# 02_ZYNQ_PS-BANK500-501.net
KiCad netlist of a schematic drawn in Altium Designer
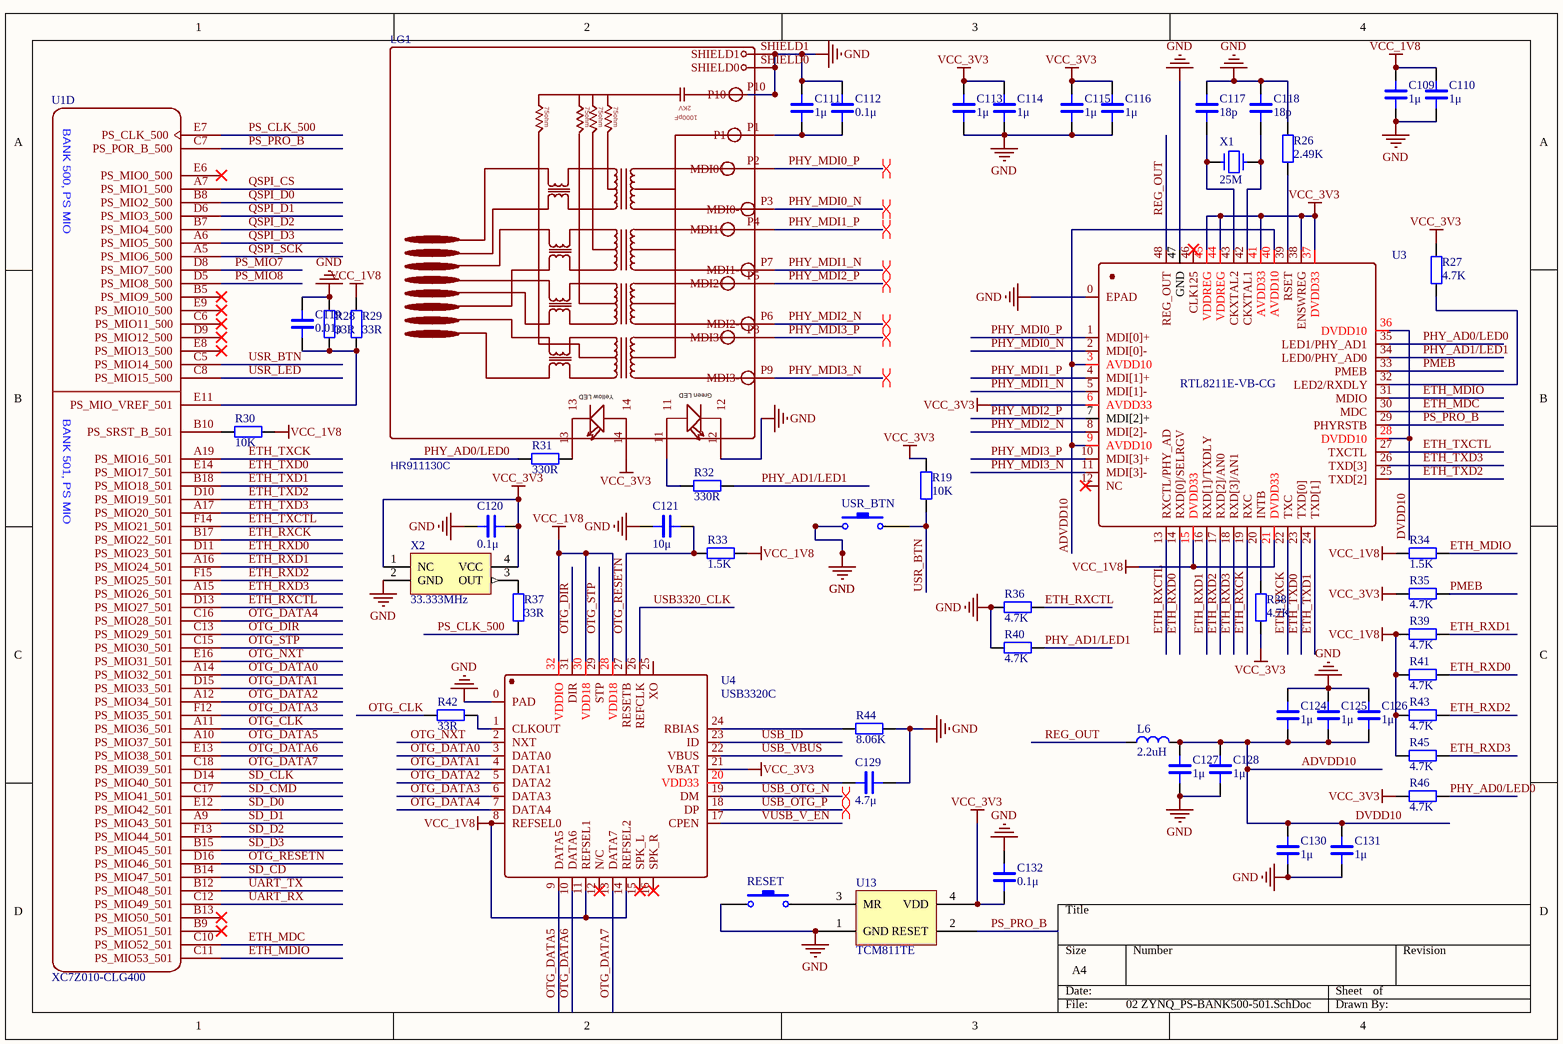
[diagram p0: 02 ZYNQ_PS-BANK500-501.SchDoc]

(export (version "E")
  (design (tool "Eeschema 10.0.6"))
  (components
    (comp (ref "C109")
      (value "1μ")
      (footprint "LC-0402_C")
      (description "Capacitor")
      (libsource (lib "DDR3_xc7z010-clg400") (part "CAP_2"))
    )
    (comp (ref "C110")
      (value "1μ")
      (footprint "LC-0402_C")
      (description "Capacitor")
      (libsource (lib "DDR3_xc7z010-clg400") (part "CAP_2"))
    )
    (comp (ref "C111")
      (value "1μ")
      (footprint "LC-0402_C")
      (description "Capacitor")
      (libsource (lib "DDR3_xc7z010-clg400") (part "CAP_2"))
    )
    (comp (ref "C112")
      (value "0.1μ")
      (footprint "LC-0402_C")
      (description "Capacitor")
      (libsource (lib "DDR3_xc7z010-clg400") (part "CAP_2"))
    )
    (comp (ref "C113")
      (value "1μ")
      (footprint "LC-0402_C")
      (description "Capacitor")
      (libsource (lib "DDR3_xc7z010-clg400") (part "CAP_2"))
    )
    (comp (ref "C114")
      (value "1μ")
      (footprint "LC-0402_C")
      (description "Capacitor")
      (libsource (lib "DDR3_xc7z010-clg400") (part "CAP_2"))
    )
    (comp (ref "C115")
      (value "1μ")
      (footprint "LC-0402_C")
      (description "Capacitor")
      (libsource (lib "DDR3_xc7z010-clg400") (part "CAP_2"))
    )
    (comp (ref "C116")
      (value "1μ")
      (footprint "LC-0402_C")
      (description "Capacitor")
      (libsource (lib "DDR3_xc7z010-clg400") (part "CAP_2"))
    )
    (comp (ref "C117")
      (value "18p")
      (footprint "LC-0402_C")
      (description "Capacitor")
      (libsource (lib "DDR3_xc7z010-clg400") (part "CAP_1"))
    )
    (comp (ref "C118")
      (value "18p")
      (footprint "LC-0402_C")
      (description "Capacitor")
      (libsource (lib "DDR3_xc7z010-clg400") (part "CAP_1"))
    )
    (comp (ref "C119")
      (value "0.01μ")
      (footprint "LC-0402_C")
      (description "Capacitor")
      (libsource (lib "DDR3_xc7z010-clg400") (part "CAP_2"))
    )
    (comp (ref "C120")
      (value "0.1μ")
      (footprint "LC-0402_C")
      (description "Capacitor")
      (libsource (lib "DDR3_xc7z010-clg400") (part "CAP_2"))
    )
    (comp (ref "C121")
      (value "10μ")
      (footprint "LC-0402_C")
      (description "Capacitor")
      (libsource (lib "DDR3_xc7z010-clg400") (part "CAP_2"))
    )
    (comp (ref "C124")
      (value "1μ")
      (footprint "LC-0402_C")
      (description "Capacitor")
      (libsource (lib "DDR3_xc7z010-clg400") (part "CAP_2"))
    )
    (comp (ref "C125")
      (value "1μ")
      (footprint "LC-0402_C")
      (description "Capacitor")
      (libsource (lib "DDR3_xc7z010-clg400") (part "CAP_2"))
    )
    (comp (ref "C126")
      (value "1μ")
      (footprint "LC-0402_C")
      (description "Capacitor")
      (libsource (lib "DDR3_xc7z010-clg400") (part "CAP_2"))
    )
    (comp (ref "C127")
      (value "1μ")
      (footprint "LC-0402_C")
      (description "Capacitor")
      (libsource (lib "DDR3_xc7z010-clg400") (part "CAP_2"))
    )
    (comp (ref "C128")
      (value "1μ")
      (footprint "LC-0402_C")
      (description "Capacitor")
      (libsource (lib "DDR3_xc7z010-clg400") (part "CAP_2"))
    )
    (comp (ref "C129")
      (value "4.7μ")
      (footprint "LC-0402_C")
      (description "Capacitor")
      (libsource (lib "DDR3_xc7z010-clg400") (part "CAP_2"))
    )
    (comp (ref "C130")
      (value "1μ")
      (footprint "LC-0402_C")
      (description "Capacitor")
      (libsource (lib "DDR3_xc7z010-clg400") (part "CAP_2"))
    )
    (comp (ref "C131")
      (value "1μ")
      (footprint "LC-0402_C")
      (description "Capacitor")
      (libsource (lib "DDR3_xc7z010-clg400") (part "CAP_2"))
    )
    (comp (ref "C132")
      (value "0.1μ")
      (footprint "LC-0402_C")
      (description "Capacitor")
      (libsource (lib "DDR3_xc7z010-clg400") (part "CAP_2"))
    )
    (comp (ref "L6")
      (value "2.2uH")
      (footprint "L1008")
      (description "Inductance")
      (libsource (lib "NGFF_M_Key_xc7z010-clg400") (part "INDUCTANCE_1"))
    )
    (comp (ref "LG1")
      (value "HR911130C")
      (footprint "HR911130C")
      (fields (field (name "BOM_SUPPLIER PART") "C50933") (field (name "CONTRIBUTOR") "LCSC"))
      (libsource (lib "AD9363_ZYNQ_V2") (part "HR911130C"))
    )
    (comp (ref "R19")
      (value "10K")
      (footprint "LC-0402_R")
      (description "Resistor")
      (libsource (lib "") (part "RES_3"))
    )
    (comp (ref "R26")
      (value "2.49K")
      (footprint "LC-0402_R")
      (description "Resistor")
      (libsource (lib "") (part "RES_2"))
    )
    (comp (ref "R27")
      (value "4.7K")
      (footprint "LC-0402_R")
      (description "Resistor")
      (libsource (lib "") (part "RES_2"))
    )
    (comp (ref "R28")
      (value "33R")
      (footprint "LC-0402_R")
      (description "Resistor")
      (libsource (lib "") (part "RES_2"))
    )
    (comp (ref "R29")
      (value "33R")
      (footprint "LC-0402_R")
      (description "Resistor")
      (libsource (lib "") (part "RES_2"))
    )
    (comp (ref "R30")
      (value "10K")
      (footprint "LC-0402_R")
      (description "Resistor")
      (libsource (lib "") (part "RES_1"))
    )
    (comp (ref "R31")
      (value "330R")
      (footprint "LC-0402_R")
      (description "Resistor")
      (libsource (lib "DDR3_xc7z010-clg400") (part "RES"))
    )
    (comp (ref "R32")
      (value "330R")
      (footprint "LC-0402_R")
      (description "Resistor")
      (libsource (lib "") (part "RES_1"))
    )
    (comp (ref "R33")
      (value "1.5K")
      (footprint "LC-0402_R")
      (description "Resistor")
      (libsource (lib "DDR3_xc7z010-clg400") (part "RES"))
    )
    (comp (ref "R34")
      (value "1.5K")
      (footprint "LC-0402_R")
      (description "Resistor")
      (libsource (lib "DDR3_xc7z010-clg400") (part "RES"))
    )
    (comp (ref "R35")
      (value "4.7K")
      (footprint "LC-0402_R")
      (description "Resistor")
      (libsource (lib "DDR3_xc7z010-clg400") (part "RES"))
    )
    (comp (ref "R36")
      (value "4.7K")
      (footprint "LC-0402_R")
      (description "Resistor")
      (libsource (lib "DDR3_xc7z010-clg400") (part "RES"))
    )
    (comp (ref "R37")
      (value "33R")
      (footprint "LC-0402_R")
      (description "Resistor")
      (libsource (lib "") (part "RES_2"))
    )
    (comp (ref "R38")
      (value "4.7K")
      (footprint "LC-0402_R")
      (description "Resistor")
      (libsource (lib "") (part "RES_2"))
    )
    (comp (ref "R39")
      (value "4.7K")
      (footprint "LC-0402_R")
      (description "Resistor")
      (libsource (lib "") (part "RES_1"))
    )
    (comp (ref "R40")
      (value "4.7K")
      (footprint "LC-0402_R")
      (description "Resistor")
      (libsource (lib "DDR3_xc7z010-clg400") (part "RES"))
    )
    (comp (ref "R41")
      (value "4.7K")
      (footprint "LC-0402_R")
      (description "Resistor")
      (libsource (lib "") (part "RES_1"))
    )
    (comp (ref "R42")
      (value "33R")
      (footprint "LC-0402_R")
      (description "Resistor")
      (libsource (lib "DDR3_xc7z010-clg400") (part "RES"))
    )
    (comp (ref "R43")
      (value "4.7K")
      (footprint "LC-0402_R")
      (description "Resistor")
      (libsource (lib "") (part "RES_1"))
    )
    (comp (ref "R44")
      (value "8.06K")
      (footprint "LC-0402_R")
      (description "Resistor")
      (libsource (lib "DDR3_xc7z010-clg400") (part "RES"))
    )
    (comp (ref "R45")
      (value "4.7K")
      (footprint "LC-0402_R")
      (description "Resistor")
      (libsource (lib "") (part "RES_1"))
    )
    (comp (ref "R46")
      (value "4.7K")
      (footprint "LC-0402_R")
      (description "Resistor")
      (libsource (lib "DDR3_xc7z010-clg400") (part "RES"))
    )
    (comp (ref "RESET")
      (value "SW-PB")
      (footprint "开关")
      (description "Switch")
      (fields (field (name "PUBLISHER") "Altium Limited"))
      (libsource (lib "PCB_Project") (part "SW-PB"))
    )
    (comp (ref "U1")
      (value "XC7Z010-CLG400")
      (footprint "CLG400-0.8")
      (libsource (lib "DDR3_xc7z010-clg400") (part "XC7Z010-CLG400"))
    )
    (comp (ref "U3")
      (value "RTL8211E-VB-CG")
      (footprint "LC-QFN-48_6x6x04P")
      (libsource (lib "NGFF_M_Key_xc7z010-clg400") (part "RTL8211E-VB-CG"))
    )
    (comp (ref "U4")
      (value "USB3320C")
      (footprint "LC-QFN-32_5x5x05P")
      (libsource (lib "NGFF_M_Key_xc7z010-clg400") (part "USB3320C"))
    )
    (comp (ref "U13")
      (value "TCM811TE")
      (footprint "TCM811TERCTR")
      (libsource (lib "PCB_Project") (part "TCM811TE"))
    )
    (comp (ref "USR_BTN")
      (value "SW-PB")
      (footprint "开关")
      (description "Switch")
      (fields (field (name "PUBLISHER") "Altium Limited"))
      (libsource (lib "M4(3333)") (part "SW-PB"))
    )
    (comp (ref "X1")
      (value "25M")
      (footprint "LC-SMD-5032_2P")
      (description "Crystal")
      (libsource (lib "DDR3_xc7z010-clg400") (part "XTAL-2"))
    )
    (comp (ref "X2")
      (value "33.333MHz")
      (footprint "OSC-SMD_4P-L3.2-W2.5-BL")
      (description "Oscillator")
      (libsource (lib "DDR3_xc7z010-clg400") (part "XTAL-4"))
    )
  )
  (nets
    (net (code "1") (name "/ADVDD10") (class "Default")
      (node (ref "C124") (pin "1") (pinfunction "1_1") (pintype "passive"))
      (node (ref "C125") (pin "1") (pinfunction "1_1") (pintype "passive"))
      (node (ref "C126") (pin "1") (pinfunction "1_1") (pintype "passive"))
      (node (ref "C127") (pin "2") (pinfunction "2_2") (pintype "passive"))
      (node (ref "C128") (pin "2") (pinfunction "2_2") (pintype "passive"))
      (node (ref "C130") (pin "2") (pinfunction "2_2") (pintype "passive"))
      (node (ref "C131") (pin "2") (pinfunction "2_2") (pintype "passive"))
      (node (ref "L6") (pin "2") (pinfunction "2_2") (pintype "passive"))
      (node (ref "U3") (pin "28") (pinfunction "DVDD10_28") (pintype "passive"))
      (node (ref "U3") (pin "3") (pinfunction "AVDD10_3") (pintype "passive"))
      (node (ref "U3") (pin "36") (pinfunction "DVDD10_36") (pintype "passive"))
      (node (ref "U3") (pin "40") (pinfunction "AVDD10_40") (pintype "passive"))
      (node (ref "U3") (pin "9") (pinfunction "AVDD10_9") (pintype "passive"))
    )
    (net (code "2") (name "/ETH_MDC") (class "Default")
      (node (ref "U1") (pin "C10") (pinfunction "PS_MIO52_501_C10") (pintype "passive"))
      (node (ref "U3") (pin "30") (pinfunction "MDC_30") (pintype "passive"))
    )
    (net (code "3") (name "/ETH_MDIO") (class "Default")
      (node (ref "R34") (pin "2") (pinfunction "2_2") (pintype "passive"))
      (node (ref "U1") (pin "C11") (pinfunction "PS_MIO53_501_C11") (pintype "passive"))
      (node (ref "U3") (pin "31") (pinfunction "MDIO_31") (pintype "passive"))
    )
    (net (code "4") (name "/ETH_RXCK") (class "Default")
      (node (ref "U1") (pin "B17") (pinfunction "PS_MIO22_501_B17") (pintype "passive"))
      (node (ref "U3") (pin "19") (pinfunction "RXC_19") (pintype "passive"))
    )
    (net (code "5") (name "/ETH_RXCTL") (class "Default")
      (node (ref "R36") (pin "2") (pinfunction "2_2") (pintype "passive"))
      (node (ref "U1") (pin "D13") (pinfunction "PS_MIO27_501_D13") (pintype "passive"))
      (node (ref "U3") (pin "13") (pinfunction "RXCTL/PHY_AD_13") (pintype "passive"))
    )
    (net (code "6") (name "/ETH_RXD0") (class "Default")
      (node (ref "R41") (pin "1") (pinfunction "1_1") (pintype "passive"))
      (node (ref "U1") (pin "D11") (pinfunction "PS_MIO23_501_D11") (pintype "passive"))
      (node (ref "U3") (pin "14") (pinfunction "RXD[0]/SELRGV_14") (pintype "passive"))
    )
    (net (code "7") (name "/ETH_RXD1") (class "Default")
      (node (ref "R39") (pin "1") (pinfunction "1_1") (pintype "passive"))
      (node (ref "U1") (pin "A16") (pinfunction "PS_MIO24_501_A16") (pintype "passive"))
      (node (ref "U3") (pin "16") (pinfunction "RXD[1]/TXDLY_16") (pintype "passive"))
    )
    (net (code "8") (name "/ETH_RXD2") (class "Default")
      (node (ref "R43") (pin "1") (pinfunction "1_1") (pintype "passive"))
      (node (ref "U1") (pin "F15") (pinfunction "PS_MIO25_501_F15") (pintype "passive"))
      (node (ref "U3") (pin "17") (pinfunction "RXD[2]/AN0_17") (pintype "passive"))
    )
    (net (code "9") (name "/ETH_RXD3") (class "Default")
      (node (ref "R45") (pin "1") (pinfunction "1_1") (pintype "passive"))
      (node (ref "U1") (pin "A15") (pinfunction "PS_MIO26_501_A15") (pintype "passive"))
      (node (ref "U3") (pin "18") (pinfunction "RXD[3]/AN1_18") (pintype "passive"))
    )
    (net (code "10") (name "/ETH_TXCK") (class "Default")
      (node (ref "U1") (pin "A19") (pinfunction "PS_MIO16_501_A19") (pintype "passive"))
      (node (ref "U3") (pin "22") (pinfunction "TXC_22") (pintype "passive"))
    )
    (net (code "11") (name "/ETH_TXCTL") (class "Default")
      (node (ref "U1") (pin "F14") (pinfunction "PS_MIO21_501_F14") (pintype "passive"))
      (node (ref "U3") (pin "27") (pinfunction "TXCTL_27") (pintype "passive"))
    )
    (net (code "12") (name "/ETH_TXD0") (class "Default")
      (node (ref "U1") (pin "E14") (pinfunction "PS_MIO17_501_E14") (pintype "passive"))
      (node (ref "U3") (pin "23") (pinfunction "TXD[0]_23") (pintype "passive"))
    )
    (net (code "13") (name "/ETH_TXD1") (class "Default")
      (node (ref "U1") (pin "B18") (pinfunction "PS_MIO18_501_B18") (pintype "passive"))
      (node (ref "U3") (pin "24") (pinfunction "TXD[1]_24") (pintype "passive"))
    )
    (net (code "14") (name "/ETH_TXD2") (class "Default")
      (node (ref "U1") (pin "D10") (pinfunction "PS_MIO19_501_D10") (pintype "passive"))
      (node (ref "U3") (pin "25") (pinfunction "TXD[2]_25") (pintype "passive"))
    )
    (net (code "15") (name "/ETH_TXD3") (class "Default")
      (node (ref "U1") (pin "A17") (pinfunction "PS_MIO20_501_A17") (pintype "passive"))
      (node (ref "U3") (pin "26") (pinfunction "TXD[3]_26") (pintype "passive"))
    )
    (net (code "16") (name "/OTG_CLK") (class "Default")
      (node (ref "R42") (pin "1") (pinfunction "1_1") (pintype "passive"))
      (node (ref "U1") (pin "A11") (pinfunction "PS_MIO36_501_A11") (pintype "passive"))
    )
    (net (code "17") (name "/OTG_DATA0") (class "Default")
      (node (ref "U1") (pin "A14") (pinfunction "PS_MIO32_501_A14") (pintype "passive"))
      (node (ref "U4") (pin "3") (pinfunction "DATA0_3") (pintype "passive"))
    )
    (net (code "18") (name "/OTG_DATA1") (class "Default")
      (node (ref "U1") (pin "D15") (pinfunction "PS_MIO33_501_D15") (pintype "passive"))
      (node (ref "U4") (pin "4") (pinfunction "DATA1_4") (pintype "passive"))
    )
    (net (code "19") (name "/OTG_DATA2") (class "Default")
      (node (ref "U1") (pin "A12") (pinfunction "PS_MIO34_501_A12") (pintype "passive"))
      (node (ref "U4") (pin "5") (pinfunction "DATA2_5") (pintype "passive"))
    )
    (net (code "20") (name "/OTG_DATA3") (class "Default")
      (node (ref "U1") (pin "F12") (pinfunction "PS_MIO35_501_F12") (pintype "passive"))
      (node (ref "U4") (pin "6") (pinfunction "DATA3_6") (pintype "passive"))
    )
    (net (code "21") (name "/OTG_DATA4") (class "Default")
      (node (ref "U1") (pin "C16") (pinfunction "PS_MIO28_501_C16") (pintype "passive"))
      (node (ref "U4") (pin "7") (pinfunction "DATA4_7") (pintype "passive"))
    )
    (net (code "22") (name "/OTG_DATA5") (class "Default")
      (node (ref "U1") (pin "A10") (pinfunction "PS_MIO37_501_A10") (pintype "passive"))
      (node (ref "U4") (pin "9") (pinfunction "DATA5_9") (pintype "passive"))
    )
    (net (code "23") (name "/OTG_DATA6") (class "Default")
      (node (ref "U1") (pin "E13") (pinfunction "PS_MIO38_501_E13") (pintype "passive"))
      (node (ref "U4") (pin "10") (pinfunction "DATA6_10") (pintype "passive"))
    )
    (net (code "24") (name "/OTG_DATA7") (class "Default")
      (node (ref "U1") (pin "C18") (pinfunction "PS_MIO39_501_C18") (pintype "passive"))
      (node (ref "U4") (pin "13") (pinfunction "DATA7_13") (pintype "passive"))
    )
    (net (code "25") (name "/OTG_DIR") (class "Default")
      (node (ref "U1") (pin "C13") (pinfunction "PS_MIO29_501_C13") (pintype "passive"))
      (node (ref "U4") (pin "31") (pinfunction "DIR_31") (pintype "passive"))
    )
    (net (code "26") (name "/OTG_NXT") (class "Default")
      (node (ref "U1") (pin "E16") (pinfunction "PS_MIO31_501_E16") (pintype "passive"))
      (node (ref "U4") (pin "2") (pinfunction "NXT_2") (pintype "passive"))
    )
    (net (code "27") (name "/OTG_RESETN") (class "Default")
      (node (ref "C121") (pin "2") (pinfunction "2_2") (pintype "passive"))
      (node (ref "R33") (pin "1") (pinfunction "1_1") (pintype "passive"))
      (node (ref "U1") (pin "D16") (pinfunction "PS_MIO46_501_D16") (pintype "passive"))
      (node (ref "U4") (pin "27") (pinfunction "RESETB_27") (pintype "passive"))
    )
    (net (code "28") (name "/OTG_STP") (class "Default")
      (node (ref "U1") (pin "C15") (pinfunction "PS_MIO30_501_C15") (pintype "passive"))
      (node (ref "U4") (pin "29") (pinfunction "STP_29") (pintype "passive"))
    )
    (net (code "29") (name "/PHY_AD0{slash}LED0") (class "Default")
      (node (ref "R31") (pin "1") (pinfunction "1_1") (pintype "passive"))
      (node (ref "R46") (pin "2") (pinfunction "2_2") (pintype "passive"))
      (node (ref "U3") (pin "35") (pinfunction "LED1/PHY_AD1_35") (pintype "passive"))
    )
    (net (code "30") (name "/PHY_AD1{slash}LED1") (class "Default")
      (node (ref "R32") (pin "1") (pinfunction "1_1") (pintype "passive"))
      (node (ref "R40") (pin "2") (pinfunction "2_2") (pintype "passive"))
      (node (ref "U3") (pin "34") (pinfunction "LED0/PHY_AD0_34") (pintype "passive"))
    )
    (net (code "31") (name "/PHY_MDI0_N") (class "Default")
      (node (ref "LG1") (pin "P3") (pinfunction "MDI0-_P3") (pintype "passive"))
      (node (ref "U3") (pin "2") (pinfunction "MDI[0]-_2") (pintype "passive"))
    )
    (net (code "32") (name "/PHY_MDI0_P") (class "Default")
      (node (ref "LG1") (pin "P2") (pinfunction "MDI0+_P2") (pintype "passive"))
      (node (ref "U3") (pin "1") (pinfunction "MDI[0]+_1") (pintype "passive"))
    )
    (net (code "33") (name "/PHY_MDI1_N") (class "Default")
      (node (ref "LG1") (pin "P7") (pinfunction "MDI1-_P7") (pintype "passive"))
      (node (ref "U3") (pin "5") (pinfunction "MDI[1]-_5") (pintype "passive"))
    )
    (net (code "34") (name "/PHY_MDI1_P") (class "Default")
      (node (ref "LG1") (pin "P4") (pinfunction "MDI1+_P4") (pintype "passive"))
      (node (ref "U3") (pin "4") (pinfunction "MDI[1]+_4") (pintype "passive"))
    )
    (net (code "35") (name "/PHY_MDI2_N") (class "Default")
      (node (ref "LG1") (pin "P6") (pinfunction "MDI2-_P6") (pintype "passive"))
      (node (ref "U3") (pin "8") (pinfunction "MDI[2]-_8") (pintype "passive"))
    )
    (net (code "36") (name "/PHY_MDI2_P") (class "Default")
      (node (ref "LG1") (pin "P5") (pinfunction "MDI2+_P5") (pintype "passive"))
      (node (ref "U3") (pin "7") (pinfunction "MDI[2]+_7") (pintype "passive"))
    )
    (net (code "37") (name "/PHY_MDI3_N") (class "Default")
      (node (ref "LG1") (pin "P9") (pinfunction "MDI3-_P9") (pintype "passive"))
      (node (ref "U3") (pin "11") (pinfunction "MDI[3]-_11") (pintype "passive"))
    )
    (net (code "38") (name "/PHY_MDI3_P") (class "Default")
      (node (ref "LG1") (pin "P8") (pinfunction "MDI3+_P8") (pintype "passive"))
      (node (ref "U3") (pin "10") (pinfunction "MDI[3]+_10") (pintype "passive"))
    )
    (net (code "39") (name "/PMEB") (class "Default")
      (node (ref "R35") (pin "2") (pinfunction "2_2") (pintype "passive"))
      (node (ref "U3") (pin "33") (pinfunction "PMEB_33") (pintype "passive"))
    )
    (net (code "40") (name "/PS_CLK_500") (class "Default")
      (node (ref "R37") (pin "1") (pinfunction "1_1") (pintype "passive"))
      (node (ref "U1") (pin "E7") (pinfunction "PS_CLK_500_E7") (pintype "passive"))
    )
    (net (code "41") (name "/PS_MIO7") (class "Default")
      (node (ref "U1") (pin "D8") (pinfunction "PS_MIO7_500_D8") (pintype "passive"))
    )
    (net (code "42") (name "/PS_MIO8") (class "Default")
      (node (ref "U1") (pin "D5") (pinfunction "PS_MIO8_500_D5") (pintype "passive"))
    )
    (net (code "43") (name "/PS_PRO_B") (class "Default")
      (node (ref "U1") (pin "C7") (pinfunction "PS_POR_B_500_C7") (pintype "passive"))
      (node (ref "U13") (pin "2") (pinfunction "RESET_2") (pintype "passive"))
      (node (ref "U3") (pin "29") (pinfunction "PHYRSTB_29") (pintype "passive"))
    )
    (net (code "44") (name "/QSPI_CS") (class "Default")
      (node (ref "U1") (pin "A7") (pinfunction "PS_MIO1_500_A7") (pintype "passive"))
    )
    (net (code "45") (name "/QSPI_D0") (class "Default")
      (node (ref "U1") (pin "B8") (pinfunction "PS_MIO2_500_B8") (pintype "passive"))
    )
    (net (code "46") (name "/QSPI_D1") (class "Default")
      (node (ref "U1") (pin "D6") (pinfunction "PS_MIO3_500_D6") (pintype "passive"))
    )
    (net (code "47") (name "/QSPI_D2") (class "Default")
      (node (ref "U1") (pin "B7") (pinfunction "PS_MIO4_500_B7") (pintype "passive"))
    )
    (net (code "48") (name "/QSPI_D3") (class "Default")
      (node (ref "U1") (pin "A6") (pinfunction "PS_MIO5_500_A6") (pintype "passive"))
    )
    (net (code "49") (name "/QSPI_SCK") (class "Default")
      (node (ref "U1") (pin "A5") (pinfunction "PS_MIO6_500_A5") (pintype "passive"))
    )
    (net (code "50") (name "/REG_OUT") (class "Default")
      (node (ref "L6") (pin "1") (pinfunction "1_1") (pintype "passive"))
      (node (ref "U3") (pin "48") (pinfunction "REG_OUT_48") (pintype "passive"))
    )
    (net (code "51") (name "/SD_CD") (class "Default")
      (node (ref "U1") (pin "B14") (pinfunction "PS_MIO47_501_B14") (pintype "passive"))
    )
    (net (code "52") (name "/SD_CLK") (class "Default")
      (node (ref "U1") (pin "D14") (pinfunction "PS_MIO40_501_D14") (pintype "passive"))
    )
    (net (code "53") (name "/SD_CMD") (class "Default")
      (node (ref "U1") (pin "C17") (pinfunction "PS_MIO41_501_C17") (pintype "passive"))
    )
    (net (code "54") (name "/SD_D0") (class "Default")
      (node (ref "U1") (pin "E12") (pinfunction "PS_MIO42_501_E12") (pintype "passive"))
    )
    (net (code "55") (name "/SD_D1") (class "Default")
      (node (ref "U1") (pin "A9") (pinfunction "PS_MIO43_501_A9") (pintype "passive"))
    )
    (net (code "56") (name "/SD_D2") (class "Default")
      (node (ref "U1") (pin "F13") (pinfunction "PS_MIO44_501_F13") (pintype "passive"))
    )
    (net (code "57") (name "/SD_D3") (class "Default")
      (node (ref "U1") (pin "B15") (pinfunction "PS_MIO45_501_B15") (pintype "passive"))
    )
    (net (code "58") (name "/UART_RX") (class "Default")
      (node (ref "U1") (pin "C12") (pinfunction "PS_MIO49_501_C12") (pintype "passive"))
    )
    (net (code "59") (name "/UART_TX") (class "Default")
      (node (ref "U1") (pin "B12") (pinfunction "PS_MIO48_501_B12") (pintype "passive"))
    )
    (net (code "60") (name "/USB3320_CLK") (class "Default")
      (node (ref "U4") (pin "26") (pinfunction "REFCLK_26") (pintype "passive"))
    )
    (net (code "61") (name "/USB_ID") (class "Default")
      (node (ref "U4") (pin "23") (pinfunction "ID_23") (pintype "passive"))
    )
    (net (code "62") (name "/USB_OTG_N") (class "Default")
      (node (ref "U4") (pin "19") (pinfunction "DM_19") (pintype "passive"))
    )
    (net (code "63") (name "/USB_OTG_P") (class "Default")
      (node (ref "U4") (pin "18") (pinfunction "DP_18") (pintype "passive"))
    )
    (net (code "64") (name "/USB_VBUS") (class "Default")
      (node (ref "U4") (pin "22") (pinfunction "VBUS_22") (pintype "passive"))
    )
    (net (code "65") (name "/USR_BTN") (class "Default")
      (node (ref "R19") (pin "2") (pinfunction "2_2") (pintype "passive"))
      (node (ref "U1") (pin "C5") (pinfunction "PS_MIO14_500_C5") (pintype "passive"))
      (node (ref "USR_BTN") (pin "2") (pinfunction "2_2") (pintype "passive"))
    )
    (net (code "66") (name "/USR_LED") (class "Default")
      (node (ref "U1") (pin "C8") (pinfunction "PS_MIO15_500_C8") (pintype "passive"))
    )
    (net (code "67") (name "/VUSB_V_EN") (class "Default")
      (node (ref "U4") (pin "17") (pinfunction "CPEN_17") (pintype "passive"))
    )
    (net (code "68") (name "GND") (class "Default")
      (node (ref "C109") (pin "1") (pinfunction "1_1") (pintype "passive"))
      (node (ref "C110") (pin "1") (pinfunction "1_1") (pintype "passive"))
      (node (ref "C111") (pin "2") (pinfunction "2_2") (pintype "passive"))
      (node (ref "C112") (pin "2") (pinfunction "2_2") (pintype "passive"))
      (node (ref "C113") (pin "1") (pinfunction "1_1") (pintype "passive"))
      (node (ref "C114") (pin "1") (pinfunction "1_1") (pintype "passive"))
      (node (ref "C115") (pin "1") (pinfunction "1_1") (pintype "passive"))
      (node (ref "C116") (pin "1") (pinfunction "1_1") (pintype "passive"))
      (node (ref "C117") (pin "2") (pinfunction "2_2") (pintype "passive"))
      (node (ref "C118") (pin "2") (pinfunction "2_2") (pintype "passive"))
      (node (ref "C119") (pin "1") (pinfunction "1_1") (pintype "passive"))
      (node (ref "C120") (pin "2") (pinfunction "2_2") (pintype "passive"))
      (node (ref "C121") (pin "1") (pinfunction "1_1") (pintype "passive"))
      (node (ref "C124") (pin "2") (pinfunction "2_2") (pintype "passive"))
      (node (ref "C125") (pin "2") (pinfunction "2_2") (pintype "passive"))
      (node (ref "C126") (pin "2") (pinfunction "2_2") (pintype "passive"))
      (node (ref "C127") (pin "1") (pinfunction "1_1") (pintype "passive"))
      (node (ref "C128") (pin "1") (pinfunction "1_1") (pintype "passive"))
      (node (ref "C129") (pin "2") (pinfunction "2_2") (pintype "passive"))
      (node (ref "C130") (pin "1") (pinfunction "1_1") (pintype "passive"))
      (node (ref "C131") (pin "1") (pinfunction "1_1") (pintype "passive"))
      (node (ref "C132") (pin "2") (pinfunction "2_2") (pintype "passive"))
      (node (ref "LG1") (pin "12") (pinfunction "12_12") (pintype "passive"))
      (node (ref "LG1") (pin "P10") (pinfunction "P10_P10") (pintype "passive"))
      (node (ref "LG1") (pin "SHIELD0") (pinfunction "SHIELD0_SHIELD0") (pintype "passive"))
      (node (ref "LG1") (pin "SHIELD1") (pinfunction "SHIELD1_SHIELD1") (pintype "passive"))
      (node (ref "R26") (pin "2") (pinfunction "2_2") (pintype "passive"))
      (node (ref "R28") (pin "2") (pinfunction "2_2") (pintype "passive"))
      (node (ref "R36") (pin "1") (pinfunction "1_1") (pintype "passive"))
      (node (ref "R40") (pin "1") (pinfunction "1_1") (pintype "passive"))
      (node (ref "R44") (pin "2") (pinfunction "2_2") (pintype "passive"))
      (node (ref "RESET") (pin "1") (pinfunction "1_1") (pintype "passive"))
      (node (ref "U13") (pin "1") (pinfunction "GND_1") (pintype "passive"))
      (node (ref "U3") (pin "0") (pinfunction "EPAD_0") (pintype "passive"))
      (node (ref "U3") (pin "47") (pinfunction "GND_47") (pintype "passive"))
      (node (ref "U4") (pin "0") (pinfunction "PAD_0") (pintype "passive"))
      (node (ref "USR_BTN") (pin "1") (pinfunction "1_1") (pintype "passive"))
      (node (ref "X2") (pin "2") (pinfunction "GND_2") (pintype "power_in"))
    )
    (net (code "69") (name "Net-(C111-Pad1)") (class "Default")
      (node (ref "C111") (pin "1") (pinfunction "1_1") (pintype "passive"))
      (node (ref "C112") (pin "1") (pinfunction "1_1") (pintype "passive"))
      (node (ref "LG1") (pin "P1") (pinfunction "P1_P1") (pintype "passive"))
    )
    (net (code "70") (name "Net-(LG1-Pad11)") (class "Default")
      (node (ref "LG1") (pin "11") (pinfunction "11_11") (pintype "passive"))
      (node (ref "R32") (pin "2") (pinfunction "2_2") (pintype "passive"))
    )
    (net (code "71") (name "Net-(LG1-Pad13)") (class "Default")
      (node (ref "LG1") (pin "13") (pinfunction "13_13") (pintype "passive"))
      (node (ref "R31") (pin "2") (pinfunction "2_2") (pintype "passive"))
    )
    (net (code "72") (name "Net-(U1D-PS_MIO_VREF_501)") (class "Default")
      (node (ref "C119") (pin "2") (pinfunction "2_2") (pintype "passive"))
      (node (ref "R28") (pin "1") (pinfunction "1_1") (pintype "passive"))
      (node (ref "R29") (pin "1") (pinfunction "1_1") (pintype "passive"))
      (node (ref "U1") (pin "E11") (pinfunction "PS_MIO_VREF_501_E11") (pintype "passive"))
    )
    (net (code "73") (name "Net-(U1D-PS_SRST_B_501)") (class "Default")
      (node (ref "R30") (pin "2") (pinfunction "2_2") (pintype "passive"))
      (node (ref "U1") (pin "B10") (pinfunction "PS_SRST_B_501_B10") (pintype "passive"))
    )
    (net (code "74") (name "Net-(U3-CKXTAL1)") (class "Default")
      (node (ref "C118") (pin "1") (pinfunction "1_1") (pintype "passive"))
      (node (ref "U3") (pin "42") (pinfunction "CKXTAL1_42") (pintype "passive"))
      (node (ref "X1") (pin "2") (pinfunction "2_2") (pintype "passive"))
    )
    (net (code "75") (name "Net-(U3-CKXTAL2)") (class "Default")
      (node (ref "C117") (pin "1") (pinfunction "1_1") (pintype "passive"))
      (node (ref "U3") (pin "43") (pinfunction "CKXTAL2_43") (pintype "passive"))
      (node (ref "X1") (pin "1") (pinfunction "1_1") (pintype "passive"))
    )
    (net (code "76") (name "Net-(U3-INTB)") (class "Default")
      (node (ref "R38") (pin "2") (pinfunction "2_2") (pintype "passive"))
      (node (ref "U3") (pin "20") (pinfunction "INTB_20") (pintype "passive"))
    )
    (net (code "77") (name "Net-(U3-LED2{slash}RXDLY)") (class "Default")
      (node (ref "R27") (pin "1") (pinfunction "1_1") (pintype "passive"))
      (node (ref "U3") (pin "32") (pinfunction "LED2/RXDLY_32") (pintype "passive"))
    )
    (net (code "78") (name "Net-(U3-RSET)") (class "Default")
      (node (ref "R26") (pin "1") (pinfunction "1_1") (pintype "passive"))
      (node (ref "U3") (pin "39") (pinfunction "RSET_39") (pintype "passive"))
    )
    (net (code "79") (name "Net-(U4-CLKOUT)") (class "Default")
      (node (ref "R42") (pin "2") (pinfunction "2_2") (pintype "passive"))
      (node (ref "U4") (pin "1") (pinfunction "CLKOUT_1") (pintype "passive"))
    )
    (net (code "80") (name "Net-(U4-RBIAS)") (class "Default")
      (node (ref "R44") (pin "1") (pinfunction "1_1") (pintype "passive"))
      (node (ref "U4") (pin "24") (pinfunction "RBIAS_24") (pintype "passive"))
    )
    (net (code "81") (name "Net-(U4-VDD33)") (class "Default")
      (node (ref "C129") (pin "1") (pinfunction "1_1") (pintype "passive"))
      (node (ref "U4") (pin "20") (pinfunction "VDD33_20") (pintype "passive"))
    )
    (net (code "82") (name "Net-(U13-MR)") (class "Default")
      (node (ref "RESET") (pin "2") (pinfunction "2_2") (pintype "passive"))
      (node (ref "U13") (pin "3") (pinfunction "MR_3") (pintype "passive"))
    )
    (net (code "83") (name "Net-(X2-OUT)") (class "Default")
      (node (ref "R37") (pin "2") (pinfunction "2_2") (pintype "passive"))
      (node (ref "X2") (pin "3") (pinfunction "OUT_3") (pintype "output"))
    )
    (net (code "84") (name "VCC_1V8") (class "Default")
      (node (ref "C109") (pin "2") (pinfunction "2_2") (pintype "passive"))
      (node (ref "C110") (pin "2") (pinfunction "2_2") (pintype "passive"))
      (node (ref "R29") (pin "2") (pinfunction "2_2") (pintype "passive"))
      (node (ref "R30") (pin "1") (pinfunction "1_1") (pintype "passive"))
      (node (ref "R33") (pin "2") (pinfunction "2_2") (pintype "passive"))
      (node (ref "R34") (pin "1") (pinfunction "1_1") (pintype "passive"))
      (node (ref "R39") (pin "2") (pinfunction "2_2") (pintype "passive"))
      (node (ref "R41") (pin "2") (pinfunction "2_2") (pintype "passive"))
      (node (ref "R43") (pin "2") (pinfunction "2_2") (pintype "passive"))
      (node (ref "R45") (pin "2") (pinfunction "2_2") (pintype "passive"))
      (node (ref "U3") (pin "15") (pinfunction "DVDD33_15") (pintype "passive"))
      (node (ref "U3") (pin "21") (pinfunction "DVDD33_21") (pintype "passive"))
      (node (ref "U4") (pin "11") (pinfunction "REFSEL1_11") (pintype "passive"))
      (node (ref "U4") (pin "14") (pinfunction "REFSEL2_14") (pintype "passive"))
      (node (ref "U4") (pin "28") (pinfunction "VDD18_28") (pintype "passive"))
      (node (ref "U4") (pin "30") (pinfunction "VDD18_30") (pintype "passive"))
      (node (ref "U4") (pin "32") (pinfunction "VDDIO_32") (pintype "passive"))
      (node (ref "U4") (pin "8") (pinfunction "REFSEL0_8") (pintype "passive"))
    )
    (net (code "85") (name "VCC_3V3") (class "Default")
      (node (ref "C113") (pin "2") (pinfunction "2_2") (pintype "passive"))
      (node (ref "C114") (pin "2") (pinfunction "2_2") (pintype "passive"))
      (node (ref "C115") (pin "2") (pinfunction "2_2") (pintype "passive"))
      (node (ref "C116") (pin "2") (pinfunction "2_2") (pintype "passive"))
      (node (ref "C120") (pin "1") (pinfunction "1_1") (pintype "passive"))
      (node (ref "C132") (pin "1") (pinfunction "1_1") (pintype "passive"))
      (node (ref "LG1") (pin "14") (pinfunction "14_14") (pintype "passive"))
      (node (ref "R19") (pin "1") (pinfunction "1_1") (pintype "passive"))
      (node (ref "R27") (pin "2") (pinfunction "2_2") (pintype "passive"))
      (node (ref "R35") (pin "1") (pinfunction "1_1") (pintype "passive"))
      (node (ref "R38") (pin "1") (pinfunction "1_1") (pintype "passive"))
      (node (ref "R46") (pin "1") (pinfunction "1_1") (pintype "passive"))
      (node (ref "U13") (pin "4") (pinfunction "VDD_4") (pintype "passive"))
      (node (ref "U3") (pin "37") (pinfunction "DVDD33_37") (pintype "passive"))
      (node (ref "U3") (pin "38") (pinfunction "ENSWREG_38") (pintype "passive"))
      (node (ref "U3") (pin "41") (pinfunction "AVDD33_41") (pintype "passive"))
      (node (ref "U3") (pin "44") (pinfunction "VDDREG_44") (pintype "passive"))
      (node (ref "U3") (pin "45") (pinfunction "VDDREG_45") (pintype "passive"))
      (node (ref "U3") (pin "6") (pinfunction "AVDD33_6") (pintype "passive"))
      (node (ref "U4") (pin "21") (pinfunction "VBAT_21") (pintype "passive"))
      (node (ref "X2") (pin "1") (pinfunction "NC_1") (pintype "passive"))
      (node (ref "X2") (pin "4") (pinfunction "VCC_4") (pintype "power_in"))
    )
    (net (code "86") (name "unconnected-(U1D-PS_MIO0_500-PadE6)") (class "Default")
      (node (ref "U1") (pin "E6") (pinfunction "PS_MIO0_500_E6") (pintype "passive+no_connect"))
    )
    (net (code "87") (name "unconnected-(U1D-PS_MIO9_500-PadB5)") (class "Default")
      (node (ref "U1") (pin "B5") (pinfunction "PS_MIO9_500_B5") (pintype "passive+no_connect"))
    )
    (net (code "88") (name "unconnected-(U1D-PS_MIO10_500-PadE9)") (class "Default")
      (node (ref "U1") (pin "E9") (pinfunction "PS_MIO10_500_E9") (pintype "passive+no_connect"))
    )
    (net (code "89") (name "unconnected-(U1D-PS_MIO11_500-PadC6)") (class "Default")
      (node (ref "U1") (pin "C6") (pinfunction "PS_MIO11_500_C6") (pintype "passive+no_connect"))
    )
    (net (code "90") (name "unconnected-(U1D-PS_MIO12_500-PadD9)") (class "Default")
      (node (ref "U1") (pin "D9") (pinfunction "PS_MIO12_500_D9") (pintype "passive+no_connect"))
    )
    (net (code "91") (name "unconnected-(U1D-PS_MIO13_500-PadE8)") (class "Default")
      (node (ref "U1") (pin "E8") (pinfunction "PS_MIO13_500_E8") (pintype "passive+no_connect"))
    )
    (net (code "92") (name "unconnected-(U1D-PS_MIO50_501-PadB13)") (class "Default")
      (node (ref "U1") (pin "B13") (pinfunction "PS_MIO50_501_B13") (pintype "passive+no_connect"))
    )
    (net (code "93") (name "unconnected-(U1D-PS_MIO51_501-PadB9)") (class "Default")
      (node (ref "U1") (pin "B9") (pinfunction "PS_MIO51_501_B9") (pintype "passive+no_connect"))
    )
    (net (code "94") (name "unconnected-(U3-CLK125-Pad46)") (class "Default")
      (node (ref "U3") (pin "46") (pinfunction "CLK125_46") (pintype "passive+no_connect"))
    )
    (net (code "95") (name "unconnected-(U3-NC-Pad12)") (class "Default")
      (node (ref "U3") (pin "12") (pinfunction "NC_12") (pintype "passive+no_connect"))
    )
    (net (code "96") (name "unconnected-(U4-N{slash}C-Pad12)") (class "Default")
      (node (ref "U4") (pin "12") (pinfunction "N/C_12") (pintype "passive+no_connect"))
    )
    (net (code "97") (name "unconnected-(U4-SPK_L-Pad15)") (class "Default")
      (node (ref "U4") (pin "15") (pinfunction "SPK_L_15") (pintype "passive+no_connect"))
    )
    (net (code "98") (name "unconnected-(U4-SPK_R-Pad16)") (class "Default")
      (node (ref "U4") (pin "16") (pinfunction "SPK_R_16") (pintype "passive+no_connect"))
    )
    (net (code "99") (name "unconnected-(U4-XO-Pad25)") (class "Default")
      (node (ref "U4") (pin "25") (pinfunction "XO_25") (pintype "passive"))
    )
  )
)
